# Plata.net
KiCad netlist of a schematic drawn in Altium Designer
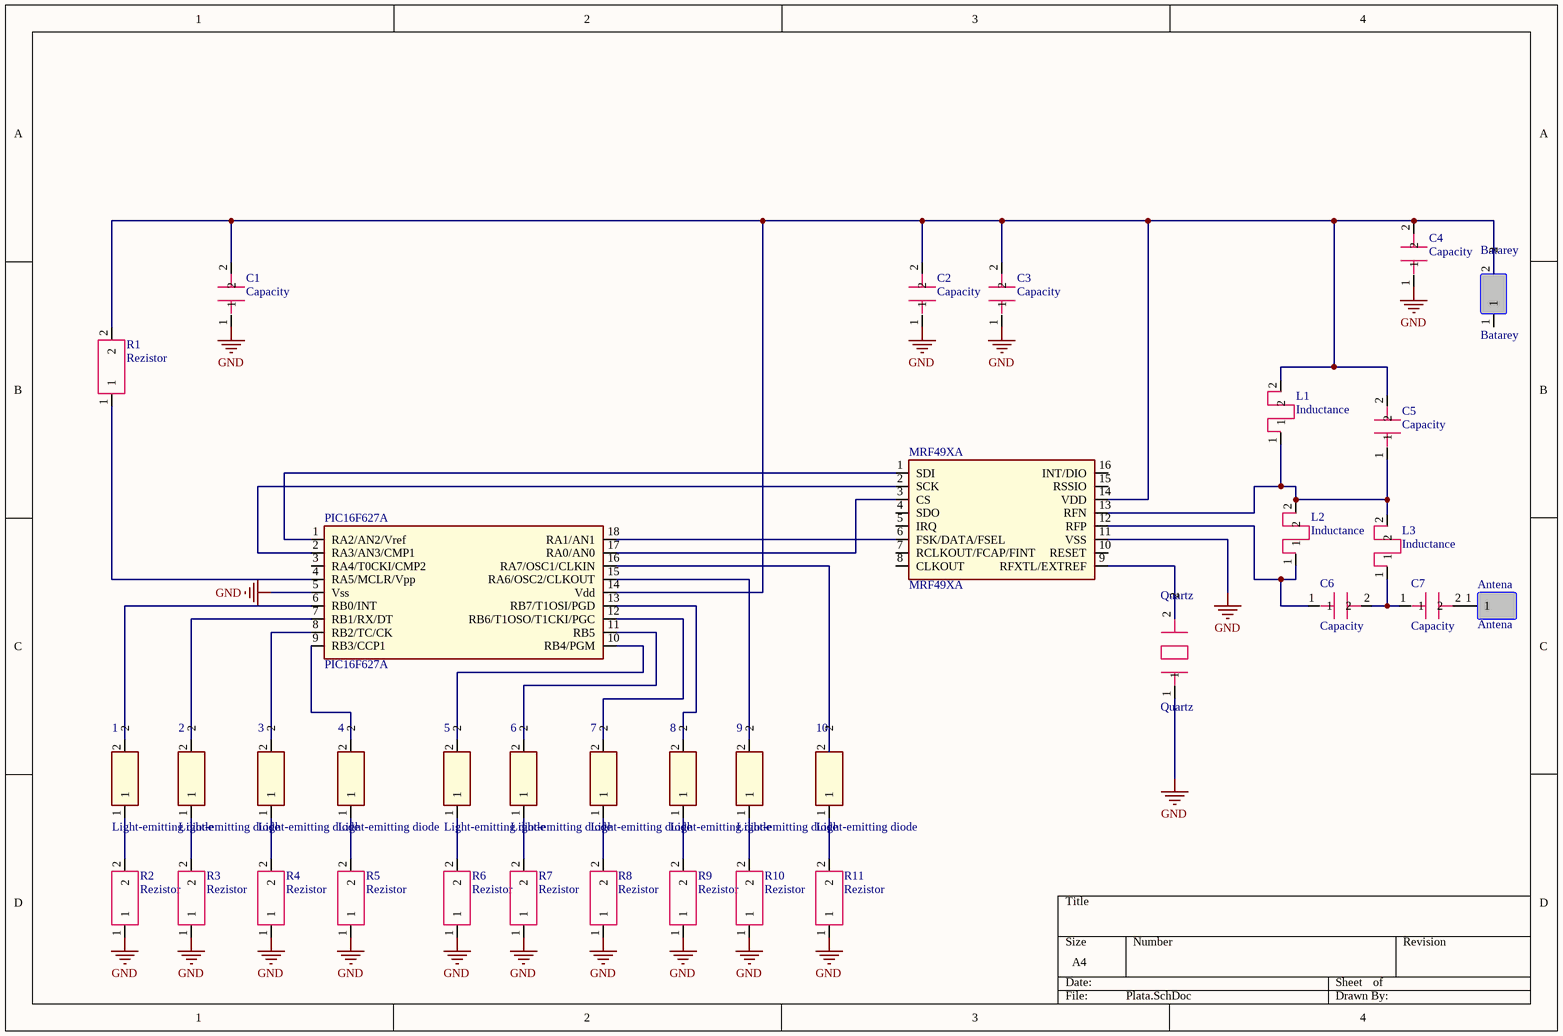
[diagram p0: Plata.SchDoc]

(export (version "E")
  (design (tool "Eeschema 10.0.6"))
  (components
    (comp (ref "1")
      (value "Light-emitting diode")
      (footprint "RCU:Light-emitting diode")
      (libsource (lib "RCU") (part "Light-emitting diode"))
    )
    (comp (ref "2")
      (value "Light-emitting diode")
      (footprint "RCU:Light-emitting diode")
      (libsource (lib "RCU") (part "Light-emitting diode"))
    )
    (comp (ref "3")
      (value "Light-emitting diode")
      (footprint "RCU:Light-emitting diode")
      (libsource (lib "RCU") (part "Light-emitting diode"))
    )
    (comp (ref "4")
      (value "Light-emitting diode")
      (footprint "RCU:Light-emitting diode")
      (libsource (lib "RCU") (part "Light-emitting diode"))
    )
    (comp (ref "5")
      (value "Light-emitting diode")
      (footprint "RCU:Light-emitting diode")
      (libsource (lib "RCU") (part "Light-emitting diode"))
    )
    (comp (ref "6")
      (value "Light-emitting diode")
      (footprint "RCU:Light-emitting diode")
      (libsource (lib "RCU") (part "Light-emitting diode"))
    )
    (comp (ref "7")
      (value "Light-emitting diode")
      (footprint "RCU:Light-emitting diode")
      (libsource (lib "RCU") (part "Light-emitting diode"))
    )
    (comp (ref "8")
      (value "Light-emitting diode")
      (footprint "RCU:Light-emitting diode")
      (libsource (lib "RCU") (part "Light-emitting diode"))
    )
    (comp (ref "9")
      (value "Light-emitting diode")
      (footprint "RCU:Light-emitting diode")
      (libsource (lib "RCU") (part "Light-emitting diode"))
    )
    (comp (ref "10")
      (value "Light-emitting diode")
      (footprint "RCU:Light-emitting diode")
      (libsource (lib "RCU") (part "Light-emitting diode"))
    )
    (comp (ref "Antena") (value "Antena") (footprint "RCU:Anteny") (libsource (lib "RCU") (part "Antena")))
    (comp (ref "Batarey")
      (value "Batarey")
      (footprint "RCU:Batarey")
      (libsource (lib "RCU") (part "Batarey"))
    )
    (comp (ref "C1") (value "Capacity") (footprint "RCU:С0805") (libsource (lib "RCU") (part "Capacity")))
    (comp (ref "C2") (value "Capacity") (footprint "RCU:С0805") (libsource (lib "RCU") (part "Capacity")))
    (comp (ref "C3") (value "Capacity") (footprint "RCU:С0805") (libsource (lib "RCU") (part "Capacity")))
    (comp (ref "C4") (value "Capacity") (footprint "RCU:С0805") (libsource (lib "RCU") (part "Capacity")))
    (comp (ref "C5") (value "Capacity") (footprint "RCU:С0805") (libsource (lib "RCU") (part "Capacity")))
    (comp (ref "C6") (value "Capacity") (footprint "RCU:С0805") (libsource (lib "RCU") (part "Capacity")))
    (comp (ref "C7") (value "Capacity") (footprint "RCU:С0805") (libsource (lib "RCU") (part "Capacity")))
    (comp (ref "L1") (value "Inductance") (footprint "RCU:L?") (libsource (lib "RCU") (part "Inductance")))
    (comp (ref "L2") (value "Inductance") (footprint "RCU:L?") (libsource (lib "RCU") (part "Inductance")))
    (comp (ref "L3") (value "Inductance") (footprint "RCU:L?") (libsource (lib "RCU") (part "Inductance")))
    (comp (ref "MRF49XA")
      (value "MRF49XA")
      (footprint "RCU:MRF49XA")
      (libsource (lib "RCU") (part "MRF49XA"))
    )
    (comp (ref "PIC16F627A")
      (value "PIC16F627A")
      (footprint "RCU:PIC16F627A")
      (libsource (lib "RCU") (part "PIC16F627A"))
    )
    (comp (ref "Quartz") (value "Quartz") (footprint "RCU:Quartz") (libsource (lib "RCU") (part "Quartz")))
    (comp (ref "R1") (value "Rezistor") (footprint "RCU:R0805") (libsource (lib "RCU") (part "Rezistor")))
    (comp (ref "R2") (value "Rezistor") (footprint "RCU:R0805") (libsource (lib "RCU") (part "Rezistor")))
    (comp (ref "R3") (value "Rezistor") (footprint "RCU:R0805") (libsource (lib "RCU") (part "Rezistor")))
    (comp (ref "R4") (value "Rezistor") (footprint "RCU:R0805") (libsource (lib "RCU") (part "Rezistor")))
    (comp (ref "R5") (value "Rezistor") (footprint "RCU:R0805") (libsource (lib "RCU") (part "Rezistor")))
    (comp (ref "R6") (value "Rezistor") (footprint "RCU:R0805") (libsource (lib "RCU") (part "Rezistor")))
    (comp (ref "R7") (value "Rezistor") (footprint "RCU:R0805") (libsource (lib "RCU") (part "Rezistor")))
    (comp (ref "R8") (value "Rezistor") (footprint "RCU:R0805") (libsource (lib "RCU") (part "Rezistor")))
    (comp (ref "R9") (value "Rezistor") (footprint "RCU:R0805") (libsource (lib "RCU") (part "Rezistor")))
    (comp (ref "R10") (value "Rezistor") (footprint "RCU:R0805") (libsource (lib "RCU") (part "Rezistor")))
    (comp (ref "R11") (value "Rezistor") (footprint "RCU:R0805") (libsource (lib "RCU") (part "Rezistor")))
  )
  (nets
    (net (code "1") (name "GND") (class "Default")
      (node (ref "C1") (pin "1") (pinfunction "1_1") (pintype "passive"))
      (node (ref "C2") (pin "1") (pinfunction "1_1") (pintype "passive"))
      (node (ref "C3") (pin "1") (pinfunction "1_1") (pintype "passive"))
      (node (ref "C4") (pin "1") (pinfunction "1_1") (pintype "passive"))
      (node (ref "MRF49XA") (pin "11") (pinfunction "VSS_11") (pintype "passive"))
      (node (ref "PIC16F627A") (pin "5") (pinfunction "Vss_5") (pintype "passive"))
      (node (ref "Quartz") (pin "1") (pinfunction "1_1") (pintype "passive"))
      (node (ref "R10") (pin "1") (pinfunction "1_1") (pintype "passive"))
      (node (ref "R11") (pin "1") (pinfunction "1_1") (pintype "passive"))
      (node (ref "R2") (pin "1") (pinfunction "1_1") (pintype "passive"))
      (node (ref "R3") (pin "1") (pinfunction "1_1") (pintype "passive"))
      (node (ref "R4") (pin "1") (pinfunction "1_1") (pintype "passive"))
      (node (ref "R5") (pin "1") (pinfunction "1_1") (pintype "passive"))
      (node (ref "R6") (pin "1") (pinfunction "1_1") (pintype "passive"))
      (node (ref "R7") (pin "1") (pinfunction "1_1") (pintype "passive"))
      (node (ref "R8") (pin "1") (pinfunction "1_1") (pintype "passive"))
      (node (ref "R9") (pin "1") (pinfunction "1_1") (pintype "passive"))
    )
    (net (code "2") (name "Net-(1-Pad1)") (class "Default")
      (node (ref "1") (pin "1") (pinfunction "1_1") (pintype "passive"))
      (node (ref "R2") (pin "2") (pinfunction "2_2") (pintype "passive"))
    )
    (net (code "3") (name "Net-(2-Pad1)") (class "Default")
      (node (ref "2") (pin "1") (pinfunction "1_1") (pintype "passive"))
      (node (ref "R3") (pin "2") (pinfunction "2_2") (pintype "passive"))
    )
    (net (code "4") (name "Net-(3-Pad1)") (class "Default")
      (node (ref "3") (pin "1") (pinfunction "1_1") (pintype "passive"))
      (node (ref "R4") (pin "2") (pinfunction "2_2") (pintype "passive"))
    )
    (net (code "5") (name "Net-(4-Pad1)") (class "Default")
      (node (ref "4") (pin "1") (pinfunction "1_1") (pintype "passive"))
      (node (ref "R5") (pin "2") (pinfunction "2_2") (pintype "passive"))
    )
    (net (code "6") (name "Net-(5-Pad1)") (class "Default")
      (node (ref "5") (pin "1") (pinfunction "1_1") (pintype "passive"))
      (node (ref "R6") (pin "2") (pinfunction "2_2") (pintype "passive"))
    )
    (net (code "7") (name "Net-(6-Pad1)") (class "Default")
      (node (ref "6") (pin "1") (pinfunction "1_1") (pintype "passive"))
      (node (ref "R7") (pin "2") (pinfunction "2_2") (pintype "passive"))
    )
    (net (code "8") (name "Net-(7-Pad1)") (class "Default")
      (node (ref "7") (pin "1") (pinfunction "1_1") (pintype "passive"))
      (node (ref "R8") (pin "2") (pinfunction "2_2") (pintype "passive"))
    )
    (net (code "9") (name "Net-(8-Pad1)") (class "Default")
      (node (ref "8") (pin "1") (pinfunction "1_1") (pintype "passive"))
      (node (ref "R9") (pin "2") (pinfunction "2_2") (pintype "passive"))
    )
    (net (code "10") (name "Net-(9-Pad1)") (class "Default")
      (node (ref "9") (pin "1") (pinfunction "1_1") (pintype "passive"))
      (node (ref "R10") (pin "2") (pinfunction "2_2") (pintype "passive"))
    )
    (net (code "11") (name "Net-(10-Pad1)") (class "Default")
      (node (ref "10") (pin "1") (pinfunction "1_1") (pintype "passive"))
      (node (ref "R11") (pin "2") (pinfunction "2_2") (pintype "passive"))
    )
    (net (code "12") (name "Net-(Antena-Pad1)") (class "Default")
      (node (ref "Antena") (pin "1") (pinfunction "1_1") (pintype "passive"))
      (node (ref "C7") (pin "2") (pinfunction "2_2") (pintype "passive"))
    )
    (net (code "13") (name "Net-(C6-Pad2)") (class "Default")
      (node (ref "C6") (pin "2") (pinfunction "2_2") (pintype "passive"))
      (node (ref "C7") (pin "1") (pinfunction "1_1") (pintype "passive"))
      (node (ref "L3") (pin "1") (pinfunction "1_1") (pintype "passive"))
    )
    (net (code "14") (name "Net-(MRF49XA-CS)") (class "Default")
      (node (ref "MRF49XA") (pin "3") (pinfunction "CS_3") (pintype "passive"))
      (node (ref "PIC16F627A") (pin "17") (pinfunction "RA0/AN0_17") (pintype "passive"))
    )
    (net (code "15") (name "Net-(MRF49XA-FSK{slash}DATA{slash}FSEL)") (class "Default")
      (node (ref "MRF49XA") (pin "6") (pinfunction "FSK/DATA/FSEL_6") (pintype "passive"))
      (node (ref "PIC16F627A") (pin "18") (pinfunction "RA1/AN1_18") (pintype "passive"))
    )
    (net (code "16") (name "Net-(MRF49XA-RFN)") (class "Default")
      (node (ref "C5") (pin "1") (pinfunction "1_1") (pintype "passive"))
      (node (ref "L1") (pin "1") (pinfunction "1_1") (pintype "passive"))
      (node (ref "L2") (pin "2") (pinfunction "2_2") (pintype "passive"))
      (node (ref "L3") (pin "2") (pinfunction "2_2") (pintype "passive"))
      (node (ref "MRF49XA") (pin "13") (pinfunction "RFN_13") (pintype "passive"))
    )
    (net (code "17") (name "Net-(MRF49XA-RFP)") (class "Default")
      (node (ref "C6") (pin "1") (pinfunction "1_1") (pintype "passive"))
      (node (ref "L2") (pin "1") (pinfunction "1_1") (pintype "passive"))
      (node (ref "MRF49XA") (pin "12") (pinfunction "RFP_12") (pintype "passive"))
    )
    (net (code "18") (name "Net-(MRF49XA-RFXTL{slash}EXTREF)") (class "Default")
      (node (ref "MRF49XA") (pin "9") (pinfunction "RFXTL/EXTREF_9") (pintype "passive"))
      (node (ref "Quartz") (pin "2") (pinfunction "2_2") (pintype "passive"))
    )
    (net (code "19") (name "Net-(MRF49XA-SCK)") (class "Default")
      (node (ref "MRF49XA") (pin "2") (pinfunction "SCK_2") (pintype "passive"))
      (node (ref "PIC16F627A") (pin "2") (pinfunction "RA3/AN3/CMP1_2") (pintype "passive"))
    )
    (net (code "20") (name "Net-(MRF49XA-SDI)") (class "Default")
      (node (ref "MRF49XA") (pin "1") (pinfunction "SDI_1") (pintype "passive"))
      (node (ref "PIC16F627A") (pin "1") (pinfunction "RA2/AN2/Vref_1") (pintype "passive"))
    )
    (net (code "21") (name "Net-(MRF49XA-VDD)") (class "Default")
      (node (ref "Batarey") (pin "2") (pinfunction "2_2") (pintype "passive"))
      (node (ref "C1") (pin "2") (pinfunction "2_2") (pintype "passive"))
      (node (ref "C2") (pin "2") (pinfunction "2_2") (pintype "passive"))
      (node (ref "C3") (pin "2") (pinfunction "2_2") (pintype "passive"))
      (node (ref "C4") (pin "2") (pinfunction "2_2") (pintype "passive"))
      (node (ref "C5") (pin "2") (pinfunction "2_2") (pintype "passive"))
      (node (ref "L1") (pin "2") (pinfunction "2_2") (pintype "passive"))
      (node (ref "MRF49XA") (pin "14") (pinfunction "VDD_14") (pintype "passive"))
      (node (ref "PIC16F627A") (pin "14") (pinfunction "Vdd_14") (pintype "passive"))
      (node (ref "R1") (pin "2") (pinfunction "2_2") (pintype "passive"))
    )
    (net (code "22") (name "Net-(PIC16F627A-RA5{slash}MCLR{slash}Vpp)") (class "Default")
      (node (ref "PIC16F627A") (pin "4") (pinfunction "RA5/MCLR/Vpp_4") (pintype "passive"))
      (node (ref "R1") (pin "1") (pinfunction "1_1") (pintype "passive"))
    )
    (net (code "23") (name "Net-(PIC16F627A-RA7{slash}OSC1{slash}CLKIN)") (class "Default")
      (node (ref "10") (pin "2") (pinfunction "2_2") (pintype "passive"))
      (node (ref "PIC16F627A") (pin "16") (pinfunction "RA7/OSC1/CLKIN_16") (pintype "passive"))
    )
    (net (code "24") (name "unconnected-(1-Pad2)") (class "Default")
      (node (ref "1") (pin "2") (pinfunction "2_2") (pintype "passive"))
    )
    (net (code "25") (name "unconnected-(2-Pad2)") (class "Default")
      (node (ref "2") (pin "2") (pinfunction "2_2") (pintype "passive"))
    )
    (net (code "26") (name "unconnected-(3-Pad2)") (class "Default")
      (node (ref "3") (pin "2") (pinfunction "2_2") (pintype "passive"))
    )
    (net (code "27") (name "unconnected-(4-Pad2)") (class "Default")
      (node (ref "4") (pin "2") (pinfunction "2_2") (pintype "passive"))
    )
    (net (code "28") (name "unconnected-(5-Pad2)") (class "Default")
      (node (ref "5") (pin "2") (pinfunction "2_2") (pintype "passive"))
    )
    (net (code "29") (name "unconnected-(6-Pad2)") (class "Default")
      (node (ref "6") (pin "2") (pinfunction "2_2") (pintype "passive"))
    )
    (net (code "30") (name "unconnected-(7-Pad2)") (class "Default")
      (node (ref "7") (pin "2") (pinfunction "2_2") (pintype "passive"))
    )
    (net (code "31") (name "unconnected-(8-Pad2)") (class "Default")
      (node (ref "8") (pin "2") (pinfunction "2_2") (pintype "passive"))
    )
    (net (code "32") (name "unconnected-(9-Pad2)") (class "Default")
      (node (ref "9") (pin "2") (pinfunction "2_2") (pintype "passive"))
    )
    (net (code "33") (name "unconnected-(Batarey-Pad1)") (class "Default")
      (node (ref "Batarey") (pin "1") (pinfunction "1_1") (pintype "passive"))
    )
    (net (code "34") (name "unconnected-(MRF49XA-CLKOUT-Pad8)") (class "Default")
      (node (ref "MRF49XA") (pin "8") (pinfunction "CLKOUT_8") (pintype "passive"))
    )
    (net (code "35") (name "unconnected-(MRF49XA-INT{slash}DIO-Pad16)") (class "Default")
      (node (ref "MRF49XA") (pin "16") (pinfunction "INT/DIO_16") (pintype "passive"))
    )
    (net (code "36") (name "unconnected-(MRF49XA-IRQ-Pad5)") (class "Default")
      (node (ref "MRF49XA") (pin "5") (pinfunction "IRQ_5") (pintype "passive"))
    )
    (net (code "37") (name "unconnected-(MRF49XA-RCLKOUT{slash}FCAP{slash}FINT-Pad7)") (class "Default")
      (node (ref "MRF49XA") (pin "7") (pinfunction "RCLKOUT/FCAP/FINT_7") (pintype "passive"))
    )
    (net (code "38") (name "unconnected-(MRF49XA-RESET-Pad10)") (class "Default")
      (node (ref "MRF49XA") (pin "10") (pinfunction "RESET_10") (pintype "passive"))
    )
    (net (code "39") (name "unconnected-(MRF49XA-RSSIO-Pad15)") (class "Default")
      (node (ref "MRF49XA") (pin "15") (pinfunction "RSSIO_15") (pintype "passive"))
    )
    (net (code "40") (name "unconnected-(MRF49XA-SDO-Pad4)") (class "Default")
      (node (ref "MRF49XA") (pin "4") (pinfunction "SDO_4") (pintype "passive"))
    )
    (net (code "41") (name "unconnected-(PIC16F627A-RA4{slash}T0CKI{slash}CMP2-Pad3)") (class "Default")
      (node (ref "PIC16F627A") (pin "3") (pinfunction "RA4/T0CKI/CMP2_3") (pintype "passive"))
    )
    (net (code "42") (name "unconnected-(PIC16F627A-RA6{slash}OSC2{slash}CLKOUT-Pad15)") (class "Default")
      (node (ref "PIC16F627A") (pin "15") (pinfunction "RA6/OSC2/CLKOUT_15") (pintype "passive"))
    )
    (net (code "43") (name "unconnected-(PIC16F627A-RB0{slash}INT-Pad6)") (class "Default")
      (node (ref "PIC16F627A") (pin "6") (pinfunction "RB0/INT_6") (pintype "passive"))
    )
    (net (code "44") (name "unconnected-(PIC16F627A-RB1{slash}RX{slash}DT-Pad7)") (class "Default")
      (node (ref "PIC16F627A") (pin "7") (pinfunction "RB1/RX/DT_7") (pintype "passive"))
    )
    (net (code "45") (name "unconnected-(PIC16F627A-RB2{slash}TC{slash}CK-Pad8)") (class "Default")
      (node (ref "PIC16F627A") (pin "8") (pinfunction "RB2/TC/CK_8") (pintype "passive"))
    )
    (net (code "46") (name "unconnected-(PIC16F627A-RB3{slash}CCP1-Pad9)") (class "Default")
      (node (ref "PIC16F627A") (pin "9") (pinfunction "RB3/CCP1_9") (pintype "passive"))
    )
    (net (code "47") (name "unconnected-(PIC16F627A-RB4{slash}PGM-Pad10)") (class "Default")
      (node (ref "PIC16F627A") (pin "10") (pinfunction "RB4/PGM_10") (pintype "passive"))
    )
    (net (code "48") (name "unconnected-(PIC16F627A-RB5-Pad11)") (class "Default")
      (node (ref "PIC16F627A") (pin "11") (pinfunction "RB5_11") (pintype "passive"))
    )
    (net (code "49") (name "unconnected-(PIC16F627A-RB6{slash}T1OSO{slash}T1CKI{slash}PGC-Pad12)") (class "Default")
      (node (ref "PIC16F627A") (pin "12") (pinfunction "RB6/T1OSO/T1CKI/PGC_12") (pintype "passive"))
    )
    (net (code "50") (name "unconnected-(PIC16F627A-RB7{slash}T1OSI{slash}PGD-Pad13)") (class "Default")
      (node (ref "PIC16F627A") (pin "13") (pinfunction "RB7/T1OSI/PGD_13") (pintype "passive"))
    )
  )
)
